# i2c_lcd.net
KiCad netlist of a schematic drawn in EAGLE
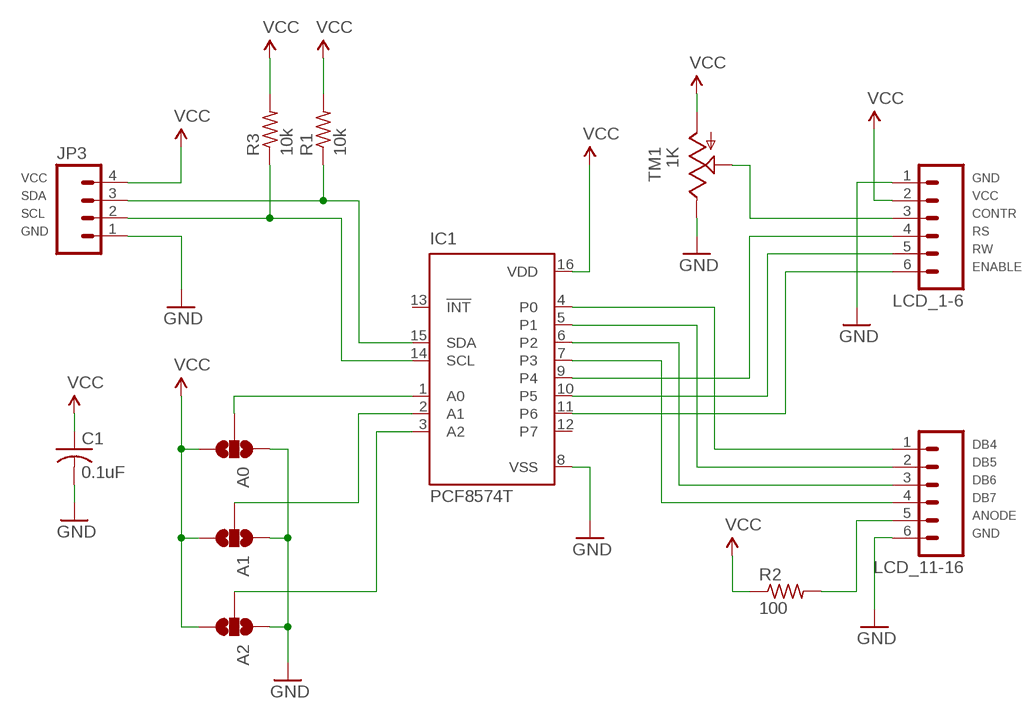
[diagram p0: schematic, sheet 1]

(export (version "E")
  (design (tool "Eeschema 10.0.6"))
  (components
    (comp (ref "A0")
      (value "SOLDERJUMPER_2WAYT")
      (footprint "eagle-import:SJ_2")
      (libsource (lib "eagle-import") (part "SOLDERJUMPER_2WAYT"))
    )
    (comp (ref "A1")
      (value "SOLDERJUMPER_2WAYT")
      (footprint "eagle-import:SJ_2")
      (libsource (lib "eagle-import") (part "SOLDERJUMPER_2WAYT"))
    )
    (comp (ref "A2")
      (value "SOLDERJUMPER_2WAYT")
      (footprint "eagle-import:SJ_2")
      (libsource (lib "eagle-import") (part "SOLDERJUMPER_2WAYT"))
    )
    (comp (ref "C1")
      (value "0.1uF")
      (footprint "eagle-import:C1206K")
      (libsource (lib "eagle-import") (part "C-USC1206K"))
    )
    (comp (ref "IC1")
      (value "PCF8574T")
      (footprint "eagle-import:SO16W")
      (fields (field (name "MPN") "PCF8574T/3,512"))
      (libsource (lib "eagle-import") (part "PCF8574T"))
    )
    (comp (ref "JP3")
      (value "M04PTH")
      (footprint "eagle-import:1X04")
      (libsource (lib "eagle-import") (part "M04PTH"))
    )
    (comp (ref "LCD_1-6")
      (value "M06SIP")
      (footprint "eagle-import:1X06")
      (libsource (lib "eagle-import") (part "M06SIP"))
    )
    (comp (ref "LCD_11-16")
      (value "M06SIP")
      (footprint "eagle-import:1X06")
      (libsource (lib "eagle-import") (part "M06SIP"))
    )
    (comp (ref "R1")
      (value "10k")
      (footprint "eagle-import:R0805")
      (libsource (lib "eagle-import") (part "R-US_R0805"))
    )
    (comp (ref "R2")
      (value "100")
      (footprint "eagle-import:R0805")
      (libsource (lib "eagle-import") (part "R-US_R0805"))
    )
    (comp (ref "R3")
      (value "10k")
      (footprint "eagle-import:R0805")
      (libsource (lib "eagle-import") (part "R-US_R0805"))
    )
    (comp (ref "TM1")
      (value "1K")
      (footprint "eagle-import:6MM")
      (libsource (lib "eagle-import") (part "TRIM"))
    )
  )
  (nets
    (net (code "1") (name "/ANODE") (class "Default")
      (node (ref "LCD_11-16") (pin "5") (pinfunction "5_5") (pintype "passive"))
      (node (ref "R2") (pin "2") (pinfunction "2_2") (pintype "passive"))
    )
    (net (code "2") (name "/CONTR") (class "Default")
      (node (ref "LCD_1-6") (pin "3") (pinfunction "3_3") (pintype "passive"))
      (node (ref "TM1") (pin "S") (pinfunction "S_S") (pintype "passive"))
    )
    (net (code "3") (name "/DB4") (class "Default")
      (node (ref "IC1") (pin "4") (pinfunction "P0_4") (pintype "bidirectional"))
      (node (ref "LCD_11-16") (pin "1") (pinfunction "1_1") (pintype "passive"))
    )
    (net (code "4") (name "/DB5") (class "Default")
      (node (ref "IC1") (pin "5") (pinfunction "P1_5") (pintype "bidirectional"))
      (node (ref "LCD_11-16") (pin "2") (pinfunction "2_2") (pintype "passive"))
    )
    (net (code "5") (name "/DB6") (class "Default")
      (node (ref "IC1") (pin "6") (pinfunction "P2_6") (pintype "bidirectional"))
      (node (ref "LCD_11-16") (pin "3") (pinfunction "3_3") (pintype "passive"))
    )
    (net (code "6") (name "/DB7") (class "Default")
      (node (ref "IC1") (pin "7") (pinfunction "P3_7") (pintype "bidirectional"))
      (node (ref "LCD_11-16") (pin "4") (pinfunction "4_4") (pintype "passive"))
    )
    (net (code "7") (name "/ENABLE") (class "Default")
      (node (ref "IC1") (pin "11") (pinfunction "P6_11") (pintype "bidirectional"))
      (node (ref "LCD_1-6") (pin "6") (pinfunction "6_6") (pintype "passive"))
    )
    (net (code "8") (name "/RS") (class "Default")
      (node (ref "IC1") (pin "9") (pinfunction "P4_9") (pintype "bidirectional"))
      (node (ref "LCD_1-6") (pin "4") (pinfunction "4_4") (pintype "passive"))
    )
    (net (code "9") (name "/RW") (class "Default")
      (node (ref "IC1") (pin "10") (pinfunction "P5_10") (pintype "bidirectional"))
      (node (ref "LCD_1-6") (pin "5") (pinfunction "5_5") (pintype "passive"))
    )
    (net (code "10") (name "/SCL") (class "Default")
      (node (ref "IC1") (pin "14") (pinfunction "SCL_14") (pintype "input"))
      (node (ref "JP3") (pin "2") (pinfunction "2_2") (pintype "passive"))
      (node (ref "R3") (pin "1") (pinfunction "1_1") (pintype "passive"))
    )
    (net (code "11") (name "/SDA") (class "Default")
      (node (ref "IC1") (pin "15") (pinfunction "SDA_15") (pintype "bidirectional"))
      (node (ref "JP3") (pin "3") (pinfunction "3_3") (pintype "passive"))
      (node (ref "R1") (pin "1") (pinfunction "1_1") (pintype "passive"))
    )
    (net (code "12") (name "GND") (class "Default")
      (node (ref "A0") (pin "1") (pinfunction "1_1") (pintype "passive"))
      (node (ref "A1") (pin "1") (pinfunction "1_1") (pintype "passive"))
      (node (ref "A2") (pin "1") (pinfunction "1_1") (pintype "passive"))
      (node (ref "C1") (pin "2") (pinfunction "2_2") (pintype "passive"))
      (node (ref "IC1") (pin "8") (pinfunction "VSS_8") (pintype "power_in"))
      (node (ref "JP3") (pin "1") (pinfunction "1_1") (pintype "passive"))
      (node (ref "LCD_1-6") (pin "1") (pinfunction "1_1") (pintype "passive"))
      (node (ref "LCD_11-16") (pin "6") (pinfunction "6_6") (pintype "passive"))
      (node (ref "TM1") (pin "E") (pinfunction "E_E") (pintype "passive"))
    )
    (net (code "13") (name "Net-(IC1-A0)") (class "Default")
      (node (ref "A0") (pin "2") (pinfunction "2_2") (pintype "passive"))
      (node (ref "IC1") (pin "1") (pinfunction "A0_1") (pintype "input"))
    )
    (net (code "14") (name "Net-(IC1-A1)") (class "Default")
      (node (ref "A1") (pin "2") (pinfunction "2_2") (pintype "passive"))
      (node (ref "IC1") (pin "2") (pinfunction "A1_2") (pintype "input"))
    )
    (net (code "15") (name "Net-(IC1-A2)") (class "Default")
      (node (ref "A2") (pin "2") (pinfunction "2_2") (pintype "passive"))
      (node (ref "IC1") (pin "3") (pinfunction "A2_3") (pintype "input"))
    )
    (net (code "16") (name "VCC") (class "Default")
      (node (ref "A0") (pin "3") (pinfunction "3_3") (pintype "passive"))
      (node (ref "A1") (pin "3") (pinfunction "3_3") (pintype "passive"))
      (node (ref "A2") (pin "3") (pinfunction "3_3") (pintype "passive"))
      (node (ref "C1") (pin "1") (pinfunction "1_1") (pintype "passive"))
      (node (ref "IC1") (pin "16") (pinfunction "VDD_16") (pintype "power_in"))
      (node (ref "JP3") (pin "4") (pinfunction "4_4") (pintype "passive"))
      (node (ref "LCD_1-6") (pin "2") (pinfunction "2_2") (pintype "passive"))
      (node (ref "R1") (pin "2") (pinfunction "2_2") (pintype "passive"))
      (node (ref "R2") (pin "1") (pinfunction "1_1") (pintype "passive"))
      (node (ref "R3") (pin "2") (pinfunction "2_2") (pintype "passive"))
      (node (ref "TM1") (pin "A") (pinfunction "A_A") (pintype "passive"))
    )
    (net (code "17") (name "unconnected-(IC1-P7-Pad12)") (class "Default")
      (node (ref "IC1") (pin "12") (pinfunction "P7_12") (pintype "bidirectional"))
    )
    (net (code "18") (name "unconnected-(IC1-~{INT}-Pad13)") (class "Default")
      (node (ref "IC1") (pin "13") (pinfunction "~{INT}_13") (pintype "output"))
    )
  )
)
